# schematic_2.net
KiCad netlist of a schematic drawn in EasyEDA
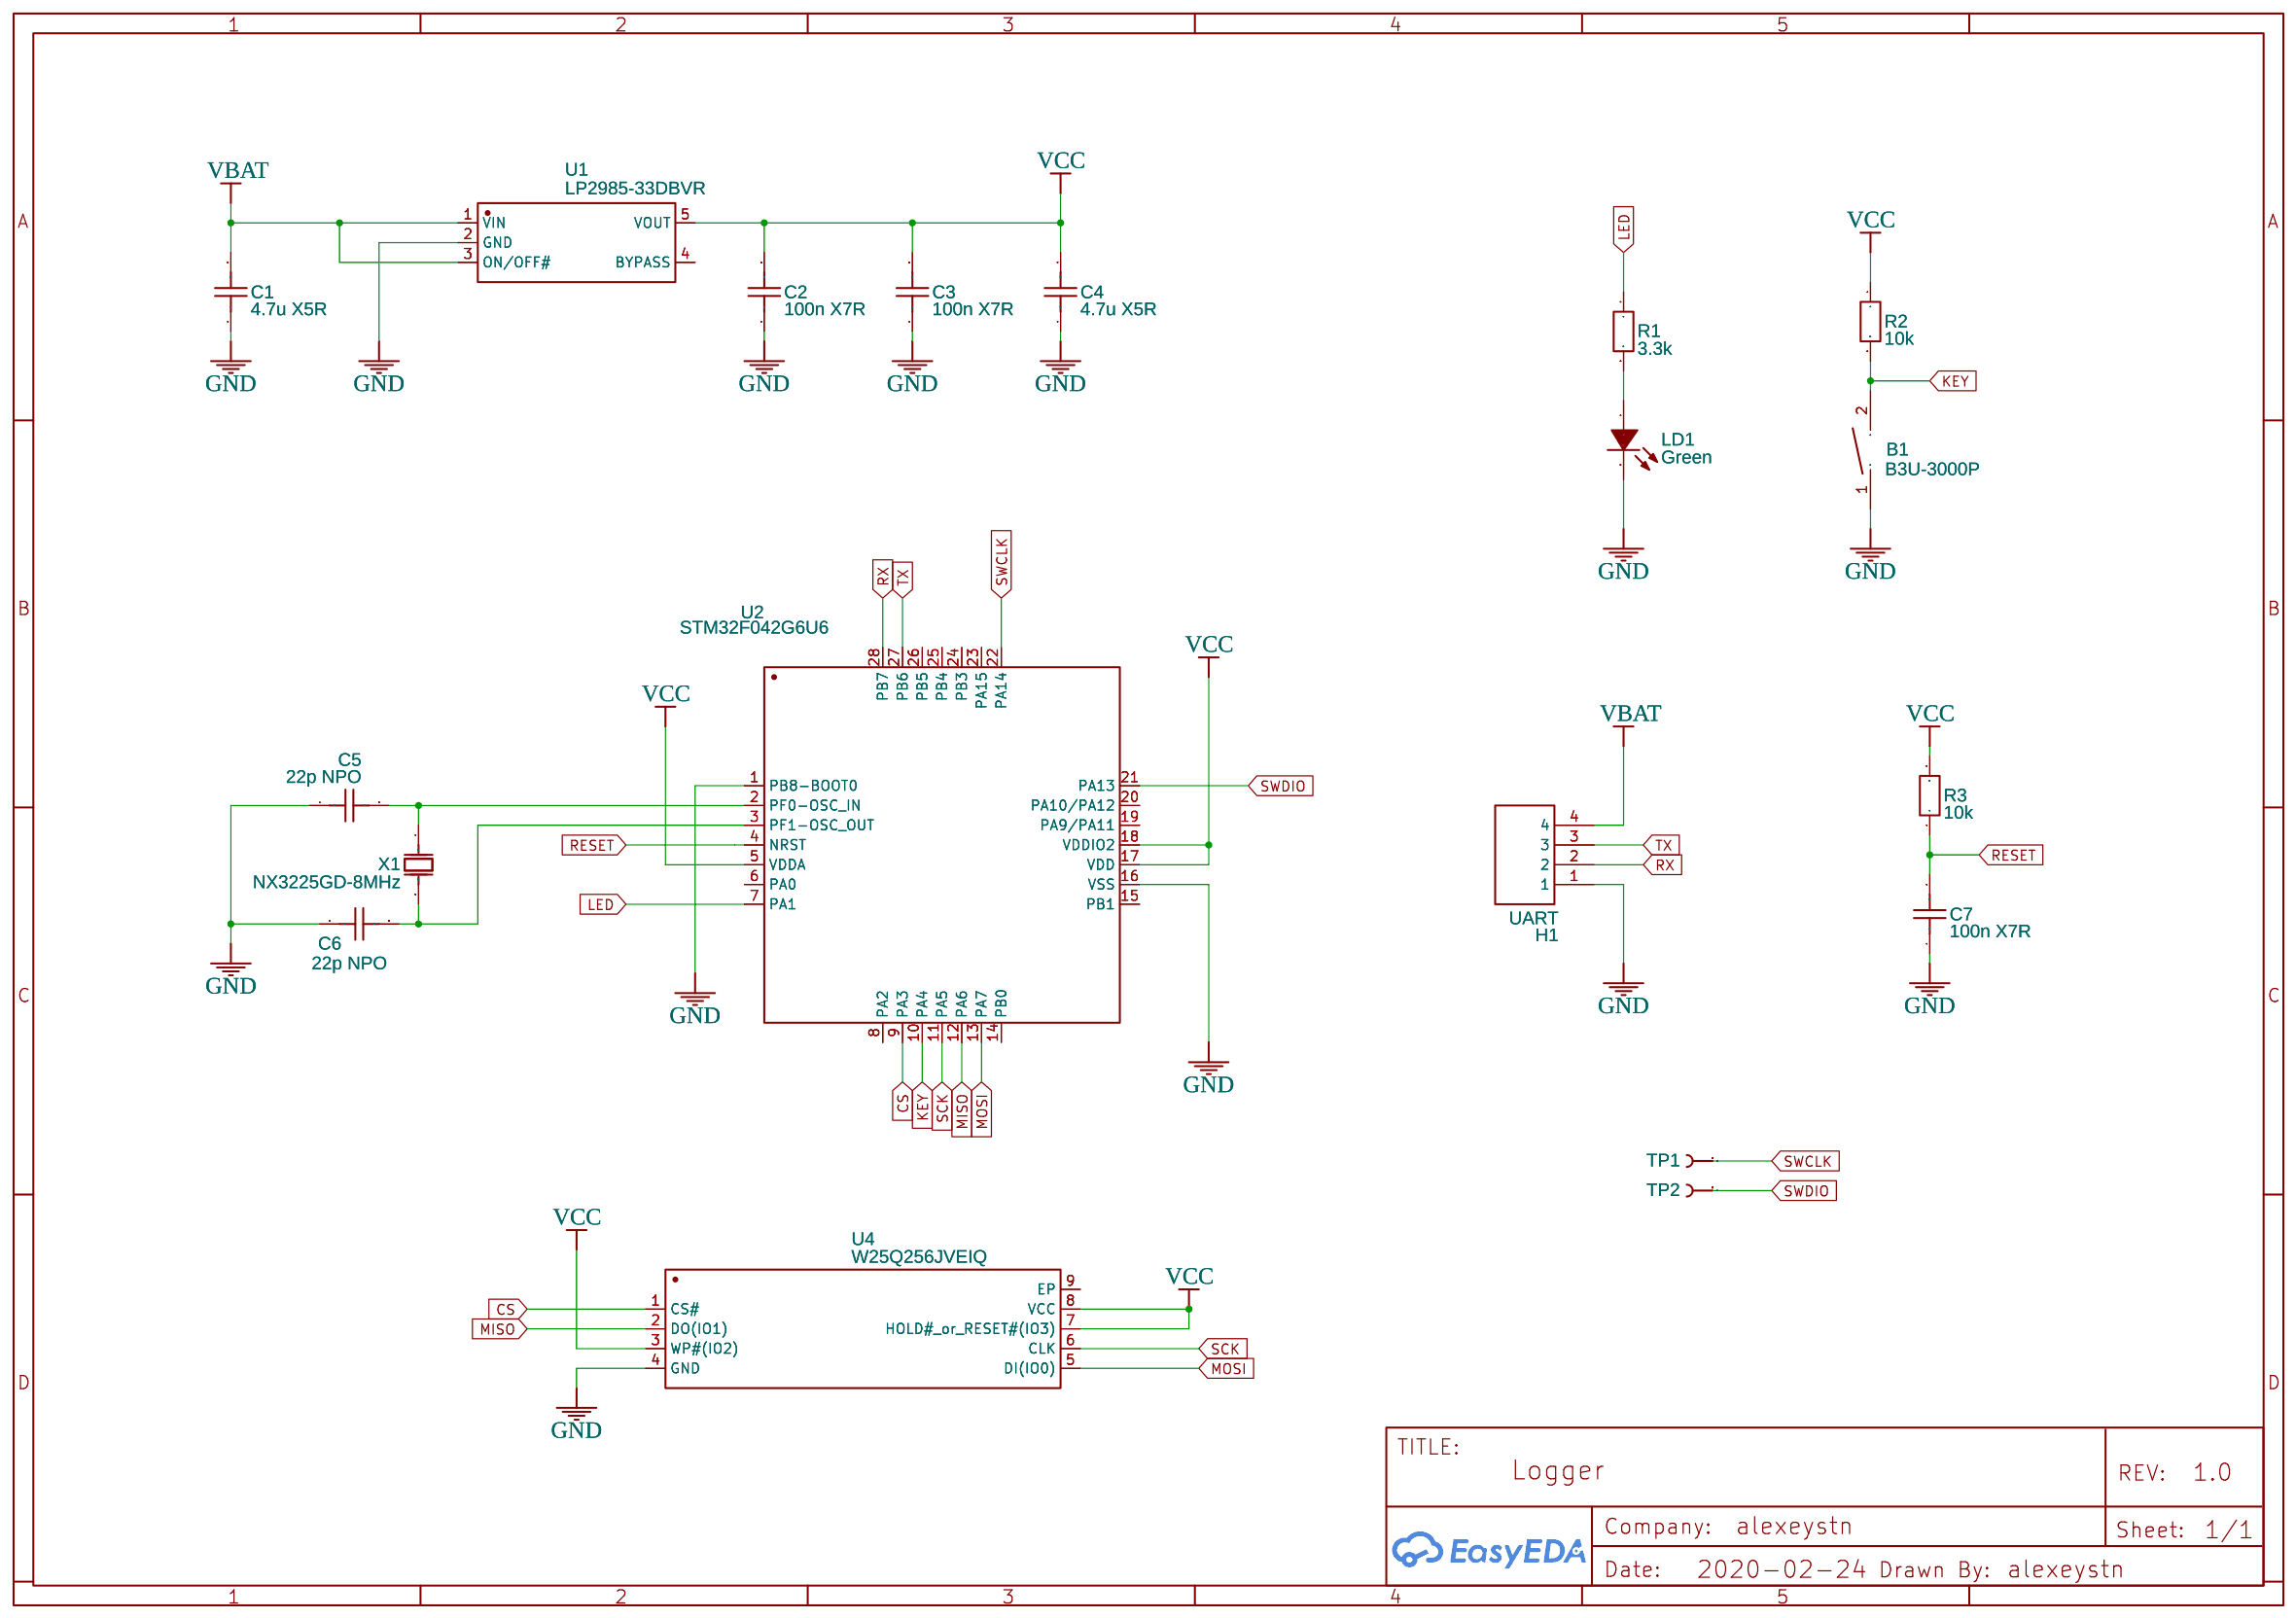
[diagram p0: schematic sheet]

(export (version "E")
  (design (tool "Eeschema 10.0.6"))
  (components
    (comp (ref "B1")
      (value "B3U-3000P")
      (fields
        (field (name "BOM_Manufacturer Part") "B3U-3000PM-B")
        (field (name "BOM_Supplier Part") "C306884")
      )
      (libsource (lib "") (part "B3U-3000PM-B"))
    )
    (comp (ref "C1") (value "4.7u X5R") (libsource (lib "") (part "Cap_0805_US_1")))
    (comp (ref "C2") (value "100n X7R") (libsource (lib "") (part "Cap_0805_US_1")))
    (comp (ref "C3") (value "100n X7R") (libsource (lib "") (part "Cap_0805_US_1")))
    (comp (ref "C4") (value "4.7u X5R") (libsource (lib "") (part "Cap_0805_US_1")))
    (comp (ref "C5") (value "22p NPO") (libsource (lib "") (part "Cap_0805_US")))
    (comp (ref "C6") (value "22p NPO") (libsource (lib "") (part "Cap_0805_US")))
    (comp (ref "C7") (value "100n X7R") (libsource (lib "") (part "Cap_0805_US_1")))
    (comp (ref "H1")
      (value "UART")
      (fields
        (field (name "BOM_Manufacturer Part") "220S-1*4P H=8.5MM Ytype Gold-plated")
        (field (name "BOM_Supplier Part") "C124413")
      )
      (libsource (lib "") (part "220S-1*4P H=8.5MM Ytype Gold-plated"))
    )
    (comp (ref "LD1")
      (value "Green")
      (fields
        (field (name "BOM_Manufacturer Part") "17-21SURC/S530-A2/TR8")
        (field (name "BOM_Supplier Part") "C131244")
      )
      (libsource (lib "") (part "17-21SURC/S530-A2/TR8"))
    )
    (comp (ref "R1") (value "3.3k") (libsource (lib "") (part "Res_0805(1/8W)_EU")))
    (comp (ref "R2") (value "10k") (libsource (lib "") (part "Res_0805(1/8W)_EU")))
    (comp (ref "R3") (value "10k") (libsource (lib "") (part "Res_0805(1/8W)_EU_1")))
    (comp (ref "TP1") (value "TEST-POINT3") (libsource (lib "") (part "TEST-POINT3")))
    (comp (ref "TP2") (value "TEST-POINT3") (libsource (lib "") (part "TEST-POINT3")))
    (comp (ref "U1")
      (value "LP2985-33DBVR")
      (fields (field (name "BOM_Supplier Part") "C95414"))
      (libsource (lib "") (part "LP2985-33DBVR"))
    )
    (comp (ref "U2")
      (value "STM32F042G6U6")
      (fields
        (field (name "BOM_Manufacturer Part") "STM32F042G4U6")
        (field (name "BOM_Supplier Part") "C88048")
      )
      (libsource (lib "") (part "STM32F042G4U6"))
    )
    (comp (ref "U4")
      (value "W25Q256JVEIQ")
      (fields (field (name "BOM_Supplier Part") "C2682312"))
      (libsource (lib "") (part "W25Q256JVEIQ"))
    )
    (comp (ref "X1") (value "NX3225GD-8MHz") (libsource (lib "") (part "NX3225GD-8MHZ-STD-CRA-3")))
  )
  (nets
    (net (code "1") (name "CS") (class "Default")
      (node (ref "U2") (pin "9") (pinfunction "PA3_9") (pintype "unspecified"))
      (node (ref "U4") (pin "1") (pinfunction "CS#_1") (pintype "unspecified"))
    )
    (net (code "2") (name "GND") (class "Default")
      (node (ref "B1") (pin "1") (pinfunction "1_1") (pintype "input"))
      (node (ref "C1") (pin "1") (pinfunction "1_1") (pintype "unspecified"))
      (node (ref "C2") (pin "1") (pinfunction "1_1") (pintype "unspecified"))
      (node (ref "C3") (pin "1") (pinfunction "1_1") (pintype "unspecified"))
      (node (ref "C4") (pin "1") (pinfunction "1_1") (pintype "unspecified"))
      (node (ref "C5") (pin "1") (pinfunction "1_1") (pintype "unspecified"))
      (node (ref "C6") (pin "1") (pinfunction "1_1") (pintype "unspecified"))
      (node (ref "C7") (pin "1") (pinfunction "1_1") (pintype "unspecified"))
      (node (ref "H1") (pin "1") (pinfunction "1_1") (pintype "unspecified"))
      (node (ref "LD1") (pin "2") (pinfunction "K_2") (pintype "unspecified"))
      (node (ref "U1") (pin "2") (pinfunction "GND_2") (pintype "unspecified"))
      (node (ref "U2") (pin "1") (pinfunction "PB8-BOOT0_1") (pintype "unspecified"))
      (node (ref "U2") (pin "16") (pinfunction "VSS_16") (pintype "unspecified"))
      (node (ref "U4") (pin "4") (pinfunction "GND_4") (pintype "unspecified"))
    )
    (net (code "3") (name "KEY") (class "Default")
      (node (ref "B1") (pin "2") (pinfunction "2_2") (pintype "input"))
      (node (ref "R2") (pin "2") (pinfunction "2_2") (pintype "unspecified"))
      (node (ref "U2") (pin "10") (pinfunction "PA4_10") (pintype "unspecified"))
    )
    (net (code "4") (name "LED") (class "Default")
      (node (ref "R1") (pin "1") (pinfunction "1_1") (pintype "unspecified"))
      (node (ref "U2") (pin "7") (pinfunction "PA1_7") (pintype "unspecified"))
    )
    (net (code "5") (name "MISO") (class "Default")
      (node (ref "U2") (pin "12") (pinfunction "PA6_12") (pintype "unspecified"))
      (node (ref "U4") (pin "2") (pinfunction "DO(IO1)_2") (pintype "unspecified"))
    )
    (net (code "6") (name "MOSI") (class "Default")
      (node (ref "U2") (pin "13") (pinfunction "PA7_13") (pintype "unspecified"))
      (node (ref "U4") (pin "5") (pinfunction "DI(IO0)_5") (pintype "unspecified"))
    )
    (net (code "7") (name "Net-(LD1-A)") (class "Default")
      (node (ref "LD1") (pin "1") (pinfunction "A_1") (pintype "unspecified"))
      (node (ref "R1") (pin "2") (pinfunction "2_2") (pintype "unspecified"))
    )
    (net (code "8") (name "Net-(U2-PF0-OSC_IN)") (class "Default")
      (node (ref "C5") (pin "2") (pinfunction "2_2") (pintype "unspecified"))
      (node (ref "U2") (pin "2") (pinfunction "PF0-OSC_IN_2") (pintype "unspecified"))
      (node (ref "X1") (pin "1") (pinfunction "OSC1_1") (pintype "input"))
    )
    (net (code "9") (name "Net-(U2-PF1-OSC_OUT)") (class "Default")
      (node (ref "C6") (pin "2") (pinfunction "2_2") (pintype "unspecified"))
      (node (ref "U2") (pin "3") (pinfunction "PF1-OSC_OUT_3") (pintype "unspecified"))
      (node (ref "X1") (pin "2") (pinfunction "OSC2_2") (pintype "input"))
    )
    (net (code "10") (name "RESET") (class "Default")
      (node (ref "C7") (pin "2") (pinfunction "2_2") (pintype "unspecified"))
      (node (ref "R3") (pin "1") (pinfunction "1_1") (pintype "unspecified"))
      (node (ref "U2") (pin "4") (pinfunction "NRST_4") (pintype "unspecified"))
    )
    (net (code "11") (name "RX") (class "Default")
      (node (ref "H1") (pin "2") (pinfunction "2_2") (pintype "unspecified"))
      (node (ref "U2") (pin "28") (pinfunction "PB7_28") (pintype "unspecified"))
    )
    (net (code "12") (name "SCK") (class "Default")
      (node (ref "U2") (pin "11") (pinfunction "PA5_11") (pintype "unspecified"))
      (node (ref "U4") (pin "6") (pinfunction "CLK_6") (pintype "unspecified"))
    )
    (net (code "13") (name "SWCLK") (class "Default")
      (node (ref "TP1") (pin "P$1") (pinfunction "1_P$1") (pintype "unspecified"))
      (node (ref "U2") (pin "22") (pinfunction "PA14_22") (pintype "unspecified"))
    )
    (net (code "14") (name "SWDIO") (class "Default")
      (node (ref "TP2") (pin "P$1") (pinfunction "1_P$1") (pintype "unspecified"))
      (node (ref "U2") (pin "21") (pinfunction "PA13_21") (pintype "unspecified"))
    )
    (net (code "15") (name "TX") (class "Default")
      (node (ref "H1") (pin "3") (pinfunction "3_3") (pintype "unspecified"))
      (node (ref "U2") (pin "27") (pinfunction "PB6_27") (pintype "unspecified"))
    )
    (net (code "16") (name "VBAT") (class "Default")
      (node (ref "C1") (pin "2") (pinfunction "2_2") (pintype "unspecified"))
      (node (ref "H1") (pin "4") (pinfunction "4_4") (pintype "unspecified"))
      (node (ref "U1") (pin "1") (pinfunction "VIN_1") (pintype "unspecified"))
      (node (ref "U1") (pin "3") (pinfunction "ON/OFF#_3") (pintype "unspecified"))
    )
    (net (code "17") (name "VCC") (class "Default")
      (node (ref "C2") (pin "2") (pinfunction "2_2") (pintype "unspecified"))
      (node (ref "C3") (pin "2") (pinfunction "2_2") (pintype "unspecified"))
      (node (ref "C4") (pin "2") (pinfunction "2_2") (pintype "unspecified"))
      (node (ref "R2") (pin "1") (pinfunction "1_1") (pintype "unspecified"))
      (node (ref "R3") (pin "2") (pinfunction "2_2") (pintype "unspecified"))
      (node (ref "U1") (pin "5") (pinfunction "VOUT_5") (pintype "unspecified"))
      (node (ref "U2") (pin "17") (pinfunction "VDD_17") (pintype "unspecified"))
      (node (ref "U2") (pin "18") (pinfunction "VDDIO2_18") (pintype "unspecified"))
      (node (ref "U2") (pin "5") (pinfunction "VDDA_5") (pintype "unspecified"))
      (node (ref "U4") (pin "3") (pinfunction "WP#(IO2)_3") (pintype "unspecified"))
      (node (ref "U4") (pin "7") (pinfunction "HOLD#_or_RESET#(IO3)_7") (pintype "unspecified"))
      (node (ref "U4") (pin "8") (pinfunction "VCC_8") (pintype "unspecified"))
    )
    (net (code "18") (name "unconnected-(U1-BYPASS-Pad4)") (class "Default")
      (node (ref "U1") (pin "4") (pinfunction "BYPASS_4") (pintype "unspecified"))
    )
    (net (code "19") (name "unconnected-(U2-PA0-Pad6)") (class "Default")
      (node (ref "U2") (pin "6") (pinfunction "PA0_6") (pintype "unspecified"))
    )
    (net (code "20") (name "unconnected-(U2-PA2-Pad8)") (class "Default")
      (node (ref "U2") (pin "8") (pinfunction "PA2_8") (pintype "unspecified"))
    )
    (net (code "21") (name "unconnected-(U2-PA9{slash}PA11-Pad19)") (class "Default")
      (node (ref "U2") (pin "19") (pinfunction "PA9/PA11_19") (pintype "unspecified"))
    )
    (net (code "22") (name "unconnected-(U2-PA10{slash}PA12-Pad20)") (class "Default")
      (node (ref "U2") (pin "20") (pinfunction "PA10/PA12_20") (pintype "unspecified"))
    )
    (net (code "23") (name "unconnected-(U2-PA15-Pad23)") (class "Default")
      (node (ref "U2") (pin "23") (pinfunction "PA15_23") (pintype "unspecified"))
    )
    (net (code "24") (name "unconnected-(U2-PB0-Pad14)") (class "Default")
      (node (ref "U2") (pin "14") (pinfunction "PB0_14") (pintype "unspecified"))
    )
    (net (code "25") (name "unconnected-(U2-PB1-Pad15)") (class "Default")
      (node (ref "U2") (pin "15") (pinfunction "PB1_15") (pintype "unspecified"))
    )
    (net (code "26") (name "unconnected-(U2-PB3-Pad24)") (class "Default")
      (node (ref "U2") (pin "24") (pinfunction "PB3_24") (pintype "unspecified"))
    )
    (net (code "27") (name "unconnected-(U2-PB4-Pad25)") (class "Default")
      (node (ref "U2") (pin "25") (pinfunction "PB4_25") (pintype "unspecified"))
    )
    (net (code "28") (name "unconnected-(U2-PB5-Pad26)") (class "Default")
      (node (ref "U2") (pin "26") (pinfunction "PB5_26") (pintype "unspecified"))
    )
    (net (code "29") (name "unconnected-(U4-EP-Pad9)") (class "Default")
      (node (ref "U4") (pin "9") (pinfunction "EP_9") (pintype "unspecified"))
    )
  )
)
